# SmartSwitchController.net
KiCad netlist of a schematic drawn in EAGLE
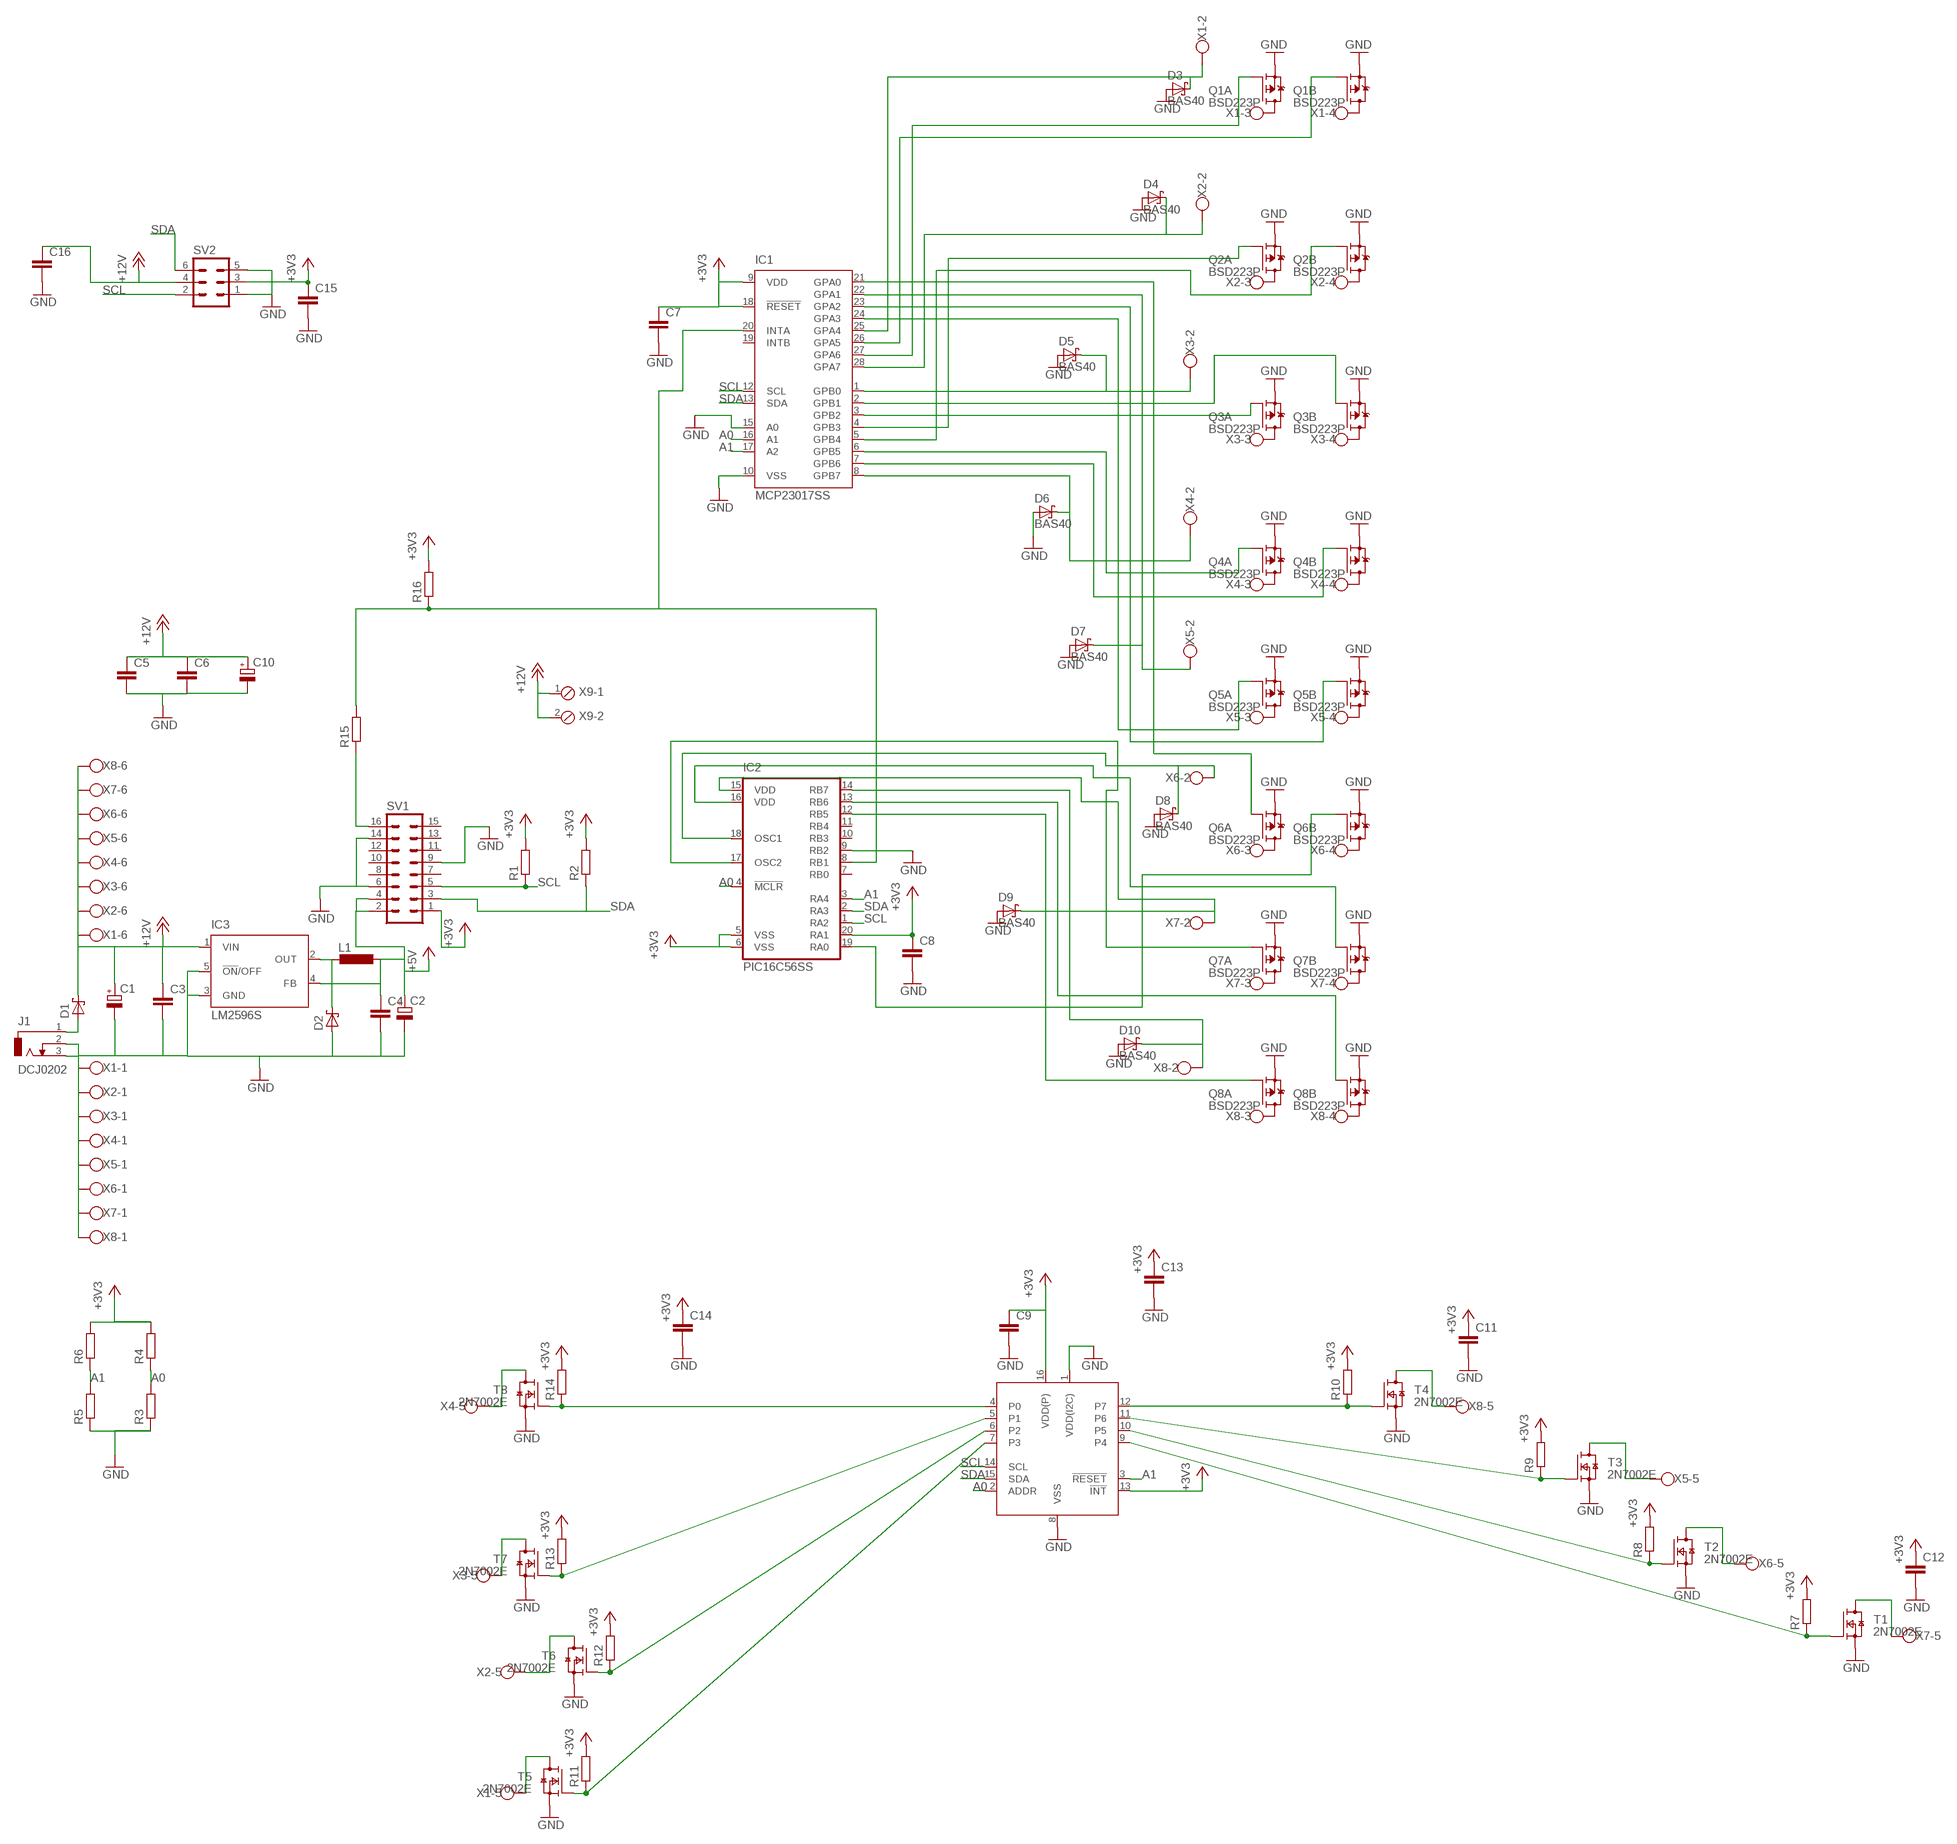
[diagram p0: schematic, sheet 1]

(export (version "E")
  (design (tool "Eeschema 10.0.6"))
  (components
    (comp (ref "C1")
      (value "CPOL-EUUD-6,3X7,7")
      (footprint "eagle-import:UD-6,3X7,7_NICHICON")
      (libsource (lib "eagle-import") (part "CPOL-EUUD-6,3X7,7"))
    )
    (comp (ref "C2")
      (value "CPOL-EUUD-10X10")
      (footprint "eagle-import:UD-10X10_NICHICON")
      (libsource (lib "eagle-import") (part "CPOL-EUUD-10X10"))
    )
    (comp (ref "C3")
      (value "C-EUC0603")
      (footprint "eagle-import:C0603")
      (libsource (lib "eagle-import") (part "C-EUC0603"))
    )
    (comp (ref "C4")
      (value "C-EUC0603")
      (footprint "eagle-import:C0603")
      (libsource (lib "eagle-import") (part "C-EUC0603"))
    )
    (comp (ref "C5")
      (value "C-EUC0603")
      (footprint "eagle-import:C0603")
      (libsource (lib "eagle-import") (part "C-EUC0603"))
    )
    (comp (ref "C6")
      (value "C-EUC0805")
      (footprint "eagle-import:C0805")
      (libsource (lib "eagle-import") (part "C-EUC0805"))
    )
    (comp (ref "C7")
      (value "C-EUC0603")
      (footprint "eagle-import:C0603")
      (libsource (lib "eagle-import") (part "C-EUC0603"))
    )
    (comp (ref "C8")
      (value "C-EUC0603")
      (footprint "eagle-import:C0603")
      (libsource (lib "eagle-import") (part "C-EUC0603"))
    )
    (comp (ref "C9")
      (value "C-EUC0603")
      (footprint "eagle-import:C0603")
      (libsource (lib "eagle-import") (part "C-EUC0603"))
    )
    (comp (ref "C10")
      (value "CPOL-EUUD-6,3X7,7")
      (footprint "eagle-import:UD-6,3X7,7_NICHICON")
      (libsource (lib "eagle-import") (part "CPOL-EUUD-6,3X7,7"))
    )
    (comp (ref "C11")
      (value "C-EUC0603")
      (footprint "eagle-import:C0603")
      (libsource (lib "eagle-import") (part "C-EUC0603"))
    )
    (comp (ref "C12")
      (value "C-EUC0603")
      (footprint "eagle-import:C0603")
      (libsource (lib "eagle-import") (part "C-EUC0603"))
    )
    (comp (ref "C13")
      (value "C-EUC0805")
      (footprint "eagle-import:C0805")
      (libsource (lib "eagle-import") (part "C-EUC0805"))
    )
    (comp (ref "C14")
      (value "C-EUC0805")
      (footprint "eagle-import:C0805")
      (libsource (lib "eagle-import") (part "C-EUC0805"))
    )
    (comp (ref "C15")
      (value "C-EUC0805")
      (footprint "eagle-import:C0805")
      (libsource (lib "eagle-import") (part "C-EUC0805"))
    )
    (comp (ref "C16")
      (value "C-EUC0805")
      (footprint "eagle-import:C0805")
      (libsource (lib "eagle-import") (part "C-EUC0805"))
    )
    (comp (ref "D1")
      (value "SCHOTTKY-DIODESMC")
      (footprint "eagle-import:SMC")
      (libsource (lib "eagle-import") (part "SCHOTTKY-DIODESMC"))
    )
    (comp (ref "D2")
      (value "SCHOTTKY-DIODESMC")
      (footprint "eagle-import:SMC")
      (libsource (lib "eagle-import") (part "SCHOTTKY-DIODESMC"))
    )
    (comp (ref "D3")
      (value "BAS40")
      (footprint "eagle-import:SOT23")
      (libsource (lib "eagle-import") (part "BAS40"))
    )
    (comp (ref "D4")
      (value "BAS40")
      (footprint "eagle-import:SOT23")
      (libsource (lib "eagle-import") (part "BAS40"))
    )
    (comp (ref "D5")
      (value "BAS40")
      (footprint "eagle-import:SOT23")
      (libsource (lib "eagle-import") (part "BAS40"))
    )
    (comp (ref "D6")
      (value "BAS40")
      (footprint "eagle-import:SOT23")
      (libsource (lib "eagle-import") (part "BAS40"))
    )
    (comp (ref "D7")
      (value "BAS40")
      (footprint "eagle-import:SOT23")
      (libsource (lib "eagle-import") (part "BAS40"))
    )
    (comp (ref "D8")
      (value "BAS40")
      (footprint "eagle-import:SOT23")
      (libsource (lib "eagle-import") (part "BAS40"))
    )
    (comp (ref "D9")
      (value "BAS40")
      (footprint "eagle-import:SOT23")
      (libsource (lib "eagle-import") (part "BAS40"))
    )
    (comp (ref "D10")
      (value "BAS40")
      (footprint "eagle-import:SOT23")
      (libsource (lib "eagle-import") (part "BAS40"))
    )
    (comp (ref "IC1")
      (value "MCP23017SS")
      (footprint "eagle-import:SSOP28")
      (fields (field (name "MF") "MICROCHIP") (field (name "MPN") "MCP23017-E/SS"))
      (libsource (lib "eagle-import") (part "MCP23017SS"))
    )
    (comp (ref "IC2")
      (value "PIC16C56SS")
      (footprint "eagle-import:SSOP20")
      (fields (field (name "MF") "MICROCHIP") (field (name "MPN") "PIC16C56A-04/SS"))
      (libsource (lib "eagle-import") (part "PIC16C56SS"))
    )
    (comp (ref "IC3")
      (value "LM2596S")
      (footprint "eagle-import:TO263-5")
      (fields (field (name "MF") "NATIONAL SEMICONDUCTOR") (field (name "MPN") "LM2596S-ADJ/NOPB"))
      (libsource (lib "eagle-import") (part "LM2596S"))
    )
    (comp (ref "J1")
      (value "DCJ0202")
      (footprint "eagle-import:DCJ0202")
      (libsource (lib "eagle-import") (part "DCJ0202"))
    )
    (comp (ref "L1")
      (value "L-EUL5650M")
      (footprint "eagle-import:L5650M")
      (libsource (lib "eagle-import") (part "L-EUL5650M"))
    )
    (comp (ref "Q1")
      (value "BSD223P")
      (footprint "eagle-import:SOT363_INFINEON")
      (libsource (lib "eagle-import") (part "BSD223P"))
    )
    (comp (ref "Q2")
      (value "BSD223P")
      (footprint "eagle-import:SOT363_INFINEON")
      (libsource (lib "eagle-import") (part "BSD223P"))
    )
    (comp (ref "Q3")
      (value "BSD223P")
      (footprint "eagle-import:SOT363_INFINEON")
      (libsource (lib "eagle-import") (part "BSD223P"))
    )
    (comp (ref "Q4")
      (value "BSD223P")
      (footprint "eagle-import:SOT363_INFINEON")
      (libsource (lib "eagle-import") (part "BSD223P"))
    )
    (comp (ref "Q5")
      (value "BSD223P")
      (footprint "eagle-import:SOT363_INFINEON")
      (libsource (lib "eagle-import") (part "BSD223P"))
    )
    (comp (ref "Q6")
      (value "BSD223P")
      (footprint "eagle-import:SOT363_INFINEON")
      (libsource (lib "eagle-import") (part "BSD223P"))
    )
    (comp (ref "Q7")
      (value "BSD223P")
      (footprint "eagle-import:SOT363_INFINEON")
      (libsource (lib "eagle-import") (part "BSD223P"))
    )
    (comp (ref "Q8")
      (value "BSD223P")
      (footprint "eagle-import:SOT363_INFINEON")
      (libsource (lib "eagle-import") (part "BSD223P"))
    )
    (comp (ref "R1")
      (value "R-EU_R0603")
      (footprint "eagle-import:R0603")
      (libsource (lib "eagle-import") (part "R-EU_R0603"))
    )
    (comp (ref "R2")
      (value "R-EU_R0603")
      (footprint "eagle-import:R0603")
      (libsource (lib "eagle-import") (part "R-EU_R0603"))
    )
    (comp (ref "R3")
      (value "R-EU_R0402")
      (footprint "eagle-import:R0402")
      (libsource (lib "eagle-import") (part "R-EU_R0402"))
    )
    (comp (ref "R4")
      (value "R-EU_R0402")
      (footprint "eagle-import:R0402")
      (libsource (lib "eagle-import") (part "R-EU_R0402"))
    )
    (comp (ref "R5")
      (value "R-EU_R0402")
      (footprint "eagle-import:R0402")
      (libsource (lib "eagle-import") (part "R-EU_R0402"))
    )
    (comp (ref "R6")
      (value "R-EU_R0402")
      (footprint "eagle-import:R0402")
      (libsource (lib "eagle-import") (part "R-EU_R0402"))
    )
    (comp (ref "R7")
      (value "R-EU_R0402")
      (footprint "eagle-import:R0402")
      (libsource (lib "eagle-import") (part "R-EU_R0402"))
    )
    (comp (ref "R8")
      (value "R-EU_R0402")
      (footprint "eagle-import:R0402")
      (libsource (lib "eagle-import") (part "R-EU_R0402"))
    )
    (comp (ref "R9")
      (value "R-EU_R0402")
      (footprint "eagle-import:R0402")
      (libsource (lib "eagle-import") (part "R-EU_R0402"))
    )
    (comp (ref "R10")
      (value "R-EU_R0402")
      (footprint "eagle-import:R0402")
      (libsource (lib "eagle-import") (part "R-EU_R0402"))
    )
    (comp (ref "R11")
      (value "R-EU_R0402")
      (footprint "eagle-import:R0402")
      (libsource (lib "eagle-import") (part "R-EU_R0402"))
    )
    (comp (ref "R12")
      (value "R-EU_R0402")
      (footprint "eagle-import:R0402")
      (libsource (lib "eagle-import") (part "R-EU_R0402"))
    )
    (comp (ref "R13")
      (value "R-EU_R0402")
      (footprint "eagle-import:R0402")
      (libsource (lib "eagle-import") (part "R-EU_R0402"))
    )
    (comp (ref "R14")
      (value "R-EU_R0402")
      (footprint "eagle-import:R0402")
      (libsource (lib "eagle-import") (part "R-EU_R0402"))
    )
    (comp (ref "R15")
      (value "R-EU_R0603")
      (footprint "eagle-import:R0603")
      (libsource (lib "eagle-import") (part "R-EU_R0603"))
    )
    (comp (ref "R16")
      (value "R-EU_R0603")
      (footprint "eagle-import:R0603")
      (libsource (lib "eagle-import") (part "R-EU_R0603"))
    )
    (comp (ref "SV1")
      (value "MA08-2")
      (footprint "eagle-import:MA08-2")
      (libsource (lib "eagle-import") (part "MA08-2"))
    )
    (comp (ref "SV2")
      (value "MA03-2")
      (footprint "eagle-import:MA03-2")
      (libsource (lib "eagle-import") (part "MA03-2"))
    )
    (comp (ref "T1")
      (value "2N7002E")
      (footprint "eagle-import:SOT23")
      (libsource (lib "eagle-import") (part "2N7002E"))
    )
    (comp (ref "T2")
      (value "2N7002E")
      (footprint "eagle-import:SOT23")
      (libsource (lib "eagle-import") (part "2N7002E"))
    )
    (comp (ref "T3")
      (value "2N7002E")
      (footprint "eagle-import:SOT23")
      (libsource (lib "eagle-import") (part "2N7002E"))
    )
    (comp (ref "T4")
      (value "2N7002E")
      (footprint "eagle-import:SOT23")
      (libsource (lib "eagle-import") (part "2N7002E"))
    )
    (comp (ref "T5")
      (value "2N7002E")
      (footprint "eagle-import:SOT23")
      (libsource (lib "eagle-import") (part "2N7002E"))
    )
    (comp (ref "T6")
      (value "2N7002E")
      (footprint "eagle-import:SOT23")
      (libsource (lib "eagle-import") (part "2N7002E"))
    )
    (comp (ref "T7")
      (value "2N7002E")
      (footprint "eagle-import:SOT23")
      (libsource (lib "eagle-import") (part "2N7002E"))
    )
    (comp (ref "T8")
      (value "2N7002E")
      (footprint "eagle-import:SOT23")
      (libsource (lib "eagle-import") (part "2N7002E"))
    )
    (comp (ref "U1")
      (value "PCAL6408APW")
      (footprint "eagle-import:SOT403-1")
      (libsource (lib "eagle-import") (part "PCAL6408APW"))
    )
    (comp (ref "X1")
      (value "W237-6")
      (footprint "eagle-import:W237-6")
      (libsource (lib "eagle-import") (part "W237-6"))
    )
    (comp (ref "X2")
      (value "W237-6")
      (footprint "eagle-import:W237-6")
      (libsource (lib "eagle-import") (part "W237-6"))
    )
    (comp (ref "X3")
      (value "W237-6")
      (footprint "eagle-import:W237-6")
      (libsource (lib "eagle-import") (part "W237-6"))
    )
    (comp (ref "X4")
      (value "W237-6")
      (footprint "eagle-import:W237-6")
      (libsource (lib "eagle-import") (part "W237-6"))
    )
    (comp (ref "X5")
      (value "W237-6")
      (footprint "eagle-import:W237-6")
      (libsource (lib "eagle-import") (part "W237-6"))
    )
    (comp (ref "X6")
      (value "W237-6")
      (footprint "eagle-import:W237-6")
      (libsource (lib "eagle-import") (part "W237-6"))
    )
    (comp (ref "X7")
      (value "W237-6")
      (footprint "eagle-import:W237-6")
      (libsource (lib "eagle-import") (part "W237-6"))
    )
    (comp (ref "X8")
      (value "W237-6")
      (footprint "eagle-import:W237-6")
      (libsource (lib "eagle-import") (part "W237-6"))
    )
    (comp (ref "X9")
      (value "MPT2")
      (footprint "eagle-import:2POL254")
      (libsource (lib "eagle-import") (part "MPT2"))
    )
  )
  (nets
    (net (code "1") (name "+3V3") (class "Default")
      (node (ref "C11") (pin "1") (pinfunction "1_1") (pintype "passive"))
      (node (ref "C12") (pin "1") (pinfunction "1_1") (pintype "passive"))
      (node (ref "C13") (pin "1") (pinfunction "1_1") (pintype "passive"))
      (node (ref "C14") (pin "1") (pinfunction "1_1") (pintype "passive"))
      (node (ref "C15") (pin "1") (pinfunction "1_1") (pintype "passive"))
      (node (ref "C7") (pin "1") (pinfunction "1_1") (pintype "passive"))
      (node (ref "C8") (pin "1") (pinfunction "1_1") (pintype "passive"))
      (node (ref "C9") (pin "1") (pinfunction "1_1") (pintype "passive"))
      (node (ref "IC1") (pin "18") (pinfunction "~{RESET}_18") (pintype "input"))
      (node (ref "IC1") (pin "9") (pinfunction "VDD_9") (pintype "power_in"))
      (node (ref "IC2") (pin "20") (pinfunction "RA1_20") (pintype "bidirectional"))
      (node (ref "IC2") (pin "5") (pinfunction "VSS_5") (pintype "power_in"))
      (node (ref "IC2") (pin "6") (pinfunction "VSS_6") (pintype "power_in"))
      (node (ref "R1") (pin "2") (pinfunction "2_2") (pintype "passive"))
      (node (ref "R10") (pin "2") (pinfunction "2_2") (pintype "passive"))
      (node (ref "R11") (pin "2") (pinfunction "2_2") (pintype "passive"))
      (node (ref "R12") (pin "2") (pinfunction "2_2") (pintype "passive"))
      (node (ref "R13") (pin "2") (pinfunction "2_2") (pintype "passive"))
      (node (ref "R14") (pin "2") (pinfunction "2_2") (pintype "passive"))
      (node (ref "R16") (pin "2") (pinfunction "2_2") (pintype "passive"))
      (node (ref "R2") (pin "2") (pinfunction "2_2") (pintype "passive"))
      (node (ref "R4") (pin "2") (pinfunction "2_2") (pintype "passive"))
      (node (ref "R6") (pin "2") (pinfunction "2_2") (pintype "passive"))
      (node (ref "R7") (pin "2") (pinfunction "2_2") (pintype "passive"))
      (node (ref "R8") (pin "2") (pinfunction "2_2") (pintype "passive"))
      (node (ref "R9") (pin "2") (pinfunction "2_2") (pintype "passive"))
      (node (ref "SV1") (pin "1") (pinfunction "1_1") (pintype "passive"))
      (node (ref "SV2") (pin "3") (pinfunction "3_3") (pintype "passive"))
      (node (ref "U1") (pin "13") (pinfunction "~{INT}_13") (pintype "output"))
      (node (ref "U1") (pin "16") (pinfunction "VDD(P)_16") (pintype "power_in"))
    )
    (net (code "2") (name "+5V") (class "Default")
      (node (ref "C2") (pin "+") (pinfunction "+_+") (pintype "passive"))
      (node (ref "C4") (pin "1") (pinfunction "1_1") (pintype "passive"))
      (node (ref "IC3") (pin "4") (pinfunction "FB_4") (pintype "input"))
      (node (ref "L1") (pin "1") (pinfunction "1_1") (pintype "passive"))
      (node (ref "SV1") (pin "2") (pinfunction "2_2") (pintype "passive"))
      (node (ref "SV1") (pin "4") (pinfunction "4_4") (pintype "passive"))
    )
    (net (code "3") (name "+12V") (class "Default")
      (node (ref "C1") (pin "+") (pinfunction "+_+") (pintype "passive"))
      (node (ref "C10") (pin "+") (pinfunction "+_+") (pintype "passive"))
      (node (ref "C16") (pin "1") (pinfunction "1_1") (pintype "passive"))
      (node (ref "C3") (pin "1") (pinfunction "1_1") (pintype "passive"))
      (node (ref "C5") (pin "1") (pinfunction "1_1") (pintype "passive"))
      (node (ref "C6") (pin "1") (pinfunction "1_1") (pintype "passive"))
      (node (ref "D1") (pin "C") (pinfunction "C_C") (pintype "passive"))
      (node (ref "IC3") (pin "1") (pinfunction "VIN_1") (pintype "input"))
      (node (ref "SV2") (pin "4") (pinfunction "4_4") (pintype "passive"))
      (node (ref "X1") (pin "6") (pinfunction "KL_6") (pintype "passive"))
      (node (ref "X2") (pin "6") (pinfunction "KL_6") (pintype "passive"))
      (node (ref "X3") (pin "6") (pinfunction "KL_6") (pintype "passive"))
      (node (ref "X4") (pin "6") (pinfunction "KL_6") (pintype "passive"))
      (node (ref "X5") (pin "6") (pinfunction "KL_6") (pintype "passive"))
      (node (ref "X6") (pin "6") (pinfunction "KL_6") (pintype "passive"))
      (node (ref "X7") (pin "6") (pinfunction "KL_6") (pintype "passive"))
      (node (ref "X8") (pin "6") (pinfunction "KL_6") (pintype "passive"))
      (node (ref "X9") (pin "1") (pinfunction "1_1") (pintype "passive"))
      (node (ref "X9") (pin "2") (pinfunction "1_2") (pintype "passive"))
    )
    (net (code "4") (name "/A0") (class "Default")
      (node (ref "IC1") (pin "16") (pinfunction "A1_16") (pintype "input"))
      (node (ref "IC2") (pin "4") (pinfunction "~{MCLR}_4") (pintype "input"))
      (node (ref "R3") (pin "2") (pinfunction "2_2") (pintype "passive"))
      (node (ref "R4") (pin "1") (pinfunction "1_1") (pintype "passive"))
      (node (ref "U1") (pin "2") (pinfunction "ADDR_2") (pintype "input"))
    )
    (net (code "5") (name "/A1") (class "Default")
      (node (ref "IC1") (pin "17") (pinfunction "A2_17") (pintype "input"))
      (node (ref "IC2") (pin "3") (pinfunction "RA4_3") (pintype "bidirectional"))
      (node (ref "R5") (pin "2") (pinfunction "2_2") (pintype "passive"))
      (node (ref "R6") (pin "1") (pinfunction "1_1") (pintype "passive"))
      (node (ref "U1") (pin "3") (pinfunction "~{RESET}_3") (pintype "input"))
    )
    (net (code "6") (name "/SCL") (class "Default")
      (node (ref "IC1") (pin "12") (pinfunction "SCL_12") (pintype "input"))
      (node (ref "IC2") (pin "1") (pinfunction "RA2_1") (pintype "bidirectional"))
      (node (ref "R1") (pin "1") (pinfunction "1_1") (pintype "passive"))
      (node (ref "SV1") (pin "5") (pinfunction "5_5") (pintype "passive"))
      (node (ref "SV2") (pin "2") (pinfunction "2_2") (pintype "passive"))
      (node (ref "U1") (pin "14") (pinfunction "SCL_14") (pintype "bidirectional"))
    )
    (net (code "7") (name "/SDA") (class "Default")
      (node (ref "IC1") (pin "13") (pinfunction "SDA_13") (pintype "bidirectional"))
      (node (ref "IC2") (pin "2") (pinfunction "RA3_2") (pintype "bidirectional"))
      (node (ref "R2") (pin "1") (pinfunction "1_1") (pintype "passive"))
      (node (ref "SV1") (pin "3") (pinfunction "3_3") (pintype "passive"))
      (node (ref "SV2") (pin "6") (pinfunction "6_6") (pintype "passive"))
      (node (ref "U1") (pin "15") (pinfunction "SDA_15") (pintype "bidirectional"))
    )
    (net (code "8") (name "GND") (class "Default")
      (node (ref "C1") (pin "-") (pinfunction "-_-") (pintype "passive"))
      (node (ref "C10") (pin "-") (pinfunction "-_-") (pintype "passive"))
      (node (ref "C11") (pin "2") (pinfunction "2_2") (pintype "passive"))
      (node (ref "C12") (pin "2") (pinfunction "2_2") (pintype "passive"))
      (node (ref "C13") (pin "2") (pinfunction "2_2") (pintype "passive"))
      (node (ref "C14") (pin "2") (pinfunction "2_2") (pintype "passive"))
      (node (ref "C15") (pin "2") (pinfunction "2_2") (pintype "passive"))
      (node (ref "C16") (pin "2") (pinfunction "2_2") (pintype "passive"))
      (node (ref "C2") (pin "-") (pinfunction "-_-") (pintype "passive"))
      (node (ref "C3") (pin "2") (pinfunction "2_2") (pintype "passive"))
      (node (ref "C4") (pin "2") (pinfunction "2_2") (pintype "passive"))
      (node (ref "C5") (pin "2") (pinfunction "2_2") (pintype "passive"))
      (node (ref "C6") (pin "2") (pinfunction "2_2") (pintype "passive"))
      (node (ref "C7") (pin "2") (pinfunction "2_2") (pintype "passive"))
      (node (ref "C8") (pin "2") (pinfunction "2_2") (pintype "passive"))
      (node (ref "C9") (pin "2") (pinfunction "2_2") (pintype "passive"))
      (node (ref "D10") (pin "1") (pinfunction "A_1") (pintype "passive"))
      (node (ref "D2") (pin "A") (pinfunction "A_A") (pintype "passive"))
      (node (ref "D3") (pin "1") (pinfunction "A_1") (pintype "passive"))
      (node (ref "D4") (pin "1") (pinfunction "A_1") (pintype "passive"))
      (node (ref "D5") (pin "1") (pinfunction "A_1") (pintype "passive"))
      (node (ref "D6") (pin "1") (pinfunction "A_1") (pintype "passive"))
      (node (ref "D7") (pin "1") (pinfunction "A_1") (pintype "passive"))
      (node (ref "D8") (pin "1") (pinfunction "A_1") (pintype "passive"))
      (node (ref "D9") (pin "1") (pinfunction "A_1") (pintype "passive"))
      (node (ref "IC1") (pin "10") (pinfunction "VSS_10") (pintype "power_in"))
      (node (ref "IC1") (pin "15") (pinfunction "A0_15") (pintype "input"))
      (node (ref "IC2") (pin "9") (pinfunction "RB2_9") (pintype "bidirectional"))
      (node (ref "IC3") (pin "3") (pinfunction "GND_3") (pintype "power_in"))
      (node (ref "IC3") (pin "5") (pinfunction "~{ON}/OFF_5") (pintype "input"))
      (node (ref "J1") (pin "2") (pinfunction "2_2") (pintype "passive"))
      (node (ref "J1") (pin "3") (pinfunction "3_3") (pintype "passive"))
      (node (ref "Q1") (pin "1") (pinfunction "S_1") (pintype "passive"))
      (node (ref "Q1") (pin "4") (pinfunction "S_4") (pintype "passive"))
      (node (ref "Q2") (pin "1") (pinfunction "S_1") (pintype "passive"))
      (node (ref "Q2") (pin "4") (pinfunction "S_4") (pintype "passive"))
      (node (ref "Q3") (pin "1") (pinfunction "S_1") (pintype "passive"))
      (node (ref "Q3") (pin "4") (pinfunction "S_4") (pintype "passive"))
      (node (ref "Q4") (pin "1") (pinfunction "S_1") (pintype "passive"))
      (node (ref "Q4") (pin "4") (pinfunction "S_4") (pintype "passive"))
      (node (ref "Q5") (pin "1") (pinfunction "S_1") (pintype "passive"))
      (node (ref "Q5") (pin "4") (pinfunction "S_4") (pintype "passive"))
      (node (ref "Q6") (pin "1") (pinfunction "S_1") (pintype "passive"))
      (node (ref "Q6") (pin "4") (pinfunction "S_4") (pintype "passive"))
      (node (ref "Q7") (pin "1") (pinfunction "S_1") (pintype "passive"))
      (node (ref "Q7") (pin "4") (pinfunction "S_4") (pintype "passive"))
      (node (ref "Q8") (pin "1") (pinfunction "S_1") (pintype "passive"))
      (node (ref "Q8") (pin "4") (pinfunction "S_4") (pintype "passive"))
      (node (ref "R3") (pin "1") (pinfunction "1_1") (pintype "passive"))
      (node (ref "R5") (pin "1") (pinfunction "1_1") (pintype "passive"))
      (node (ref "SV1") (pin "14") (pinfunction "14_14") (pintype "passive"))
      (node (ref "SV1") (pin "6") (pinfunction "6_6") (pintype "passive"))
      (node (ref "SV1") (pin "9") (pinfunction "9_9") (pintype "passive"))
      (node (ref "SV2") (pin "1") (pinfunction "1_1") (pintype "passive"))
      (node (ref "SV2") (pin "5") (pinfunction "5_5") (pintype "passive"))
      (node (ref "T1") (pin "2") (pinfunction "S_2") (pintype "passive"))
      (node (ref "T2") (pin "2") (pinfunction "S_2") (pintype "passive"))
      (node (ref "T3") (pin "2") (pinfunction "S_2") (pintype "passive"))
      (node (ref "T4") (pin "2") (pinfunction "S_2") (pintype "passive"))
      (node (ref "T5") (pin "2") (pinfunction "S_2") (pintype "passive"))
      (node (ref "T6") (pin "2") (pinfunction "S_2") (pintype "passive"))
      (node (ref "T7") (pin "2") (pinfunction "S_2") (pintype "passive"))
      (node (ref "T8") (pin "2") (pinfunction "S_2") (pintype "passive"))
      (node (ref "U1") (pin "1") (pinfunction "VDD(I2C)_1") (pintype "power_in"))
      (node (ref "U1") (pin "8") (pinfunction "VSS_8") (pintype "bidirectional"))
      (node (ref "X1") (pin "1") (pinfunction "KL_1") (pintype "passive"))
      (node (ref "X2") (pin "1") (pinfunction "KL_1") (pintype "passive"))
      (node (ref "X3") (pin "1") (pinfunction "KL_1") (pintype "passive"))
      (node (ref "X4") (pin "1") (pinfunction "KL_1") (pintype "passive"))
      (node (ref "X5") (pin "1") (pinfunction "KL_1") (pintype "passive"))
      (node (ref "X6") (pin "1") (pinfunction "KL_1") (pintype "passive"))
      (node (ref "X7") (pin "1") (pinfunction "KL_1") (pintype "passive"))
      (node (ref "X8") (pin "1") (pinfunction "KL_1") (pintype "passive"))
    )
    (net (code "9") (name "Net-(D1-PadA)") (class "Default")
      (node (ref "D1") (pin "A") (pinfunction "A_A") (pintype "passive"))
      (node (ref "J1") (pin "1") (pinfunction "1_1") (pintype "passive"))
    )
    (net (code "10") (name "Net-(D3-C)") (class "Default")
      (node (ref "D3") (pin "3") (pinfunction "C_3") (pintype "passive"))
      (node (ref "IC1") (pin "25") (pinfunction "GPA4_25") (pintype "bidirectional"))
      (node (ref "X1") (pin "2") (pinfunction "KL_2") (pintype "passive"))
    )
    (net (code "11") (name "Net-(D4-C)") (class "Default")
      (node (ref "D4") (pin "3") (pinfunction "C_3") (pintype "passive"))
      (node (ref "IC1") (pin "28") (pinfunction "GPA7_28") (pintype "bidirectional"))
      (node (ref "X2") (pin "2") (pinfunction "KL_2") (pintype "passive"))
    )
    (net (code "12") (name "Net-(D5-C)") (class "Default")
      (node (ref "D5") (pin "3") (pinfunction "C_3") (pintype "passive"))
      (node (ref "IC1") (pin "1") (pinfunction "GPB0_1") (pintype "bidirectional"))
      (node (ref "X3") (pin "2") (pinfunction "KL_2") (pintype "passive"))
    )
    (net (code "13") (name "Net-(D6-C)") (class "Default")
      (node (ref "D6") (pin "3") (pinfunction "C_3") (pintype "passive"))
      (node (ref "IC1") (pin "8") (pinfunction "GPB7_8") (pintype "bidirectional"))
      (node (ref "X4") (pin "2") (pinfunction "KL_2") (pintype "passive"))
    )
    (net (code "14") (name "Net-(D7-C)") (class "Default")
      (node (ref "D7") (pin "3") (pinfunction "C_3") (pintype "passive"))
      (node (ref "IC1") (pin "22") (pinfunction "GPA1_22") (pintype "bidirectional"))
      (node (ref "X5") (pin "2") (pinfunction "KL_2") (pintype "passive"))
    )
    (net (code "15") (name "Net-(D8-C)") (class "Default")
      (node (ref "D8") (pin "3") (pinfunction "C_3") (pintype "passive"))
      (node (ref "IC2") (pin "18") (pinfunction "OSC1_18") (pintype "input"))
      (node (ref "X6") (pin "2") (pinfunction "KL_2") (pintype "passive"))
    )
    (net (code "16") (name "Net-(D9-C)") (class "Default")
      (node (ref "D9") (pin "3") (pinfunction "C_3") (pintype "passive"))
      (node (ref "IC2") (pin "15") (pinfunction "VDD_15") (pintype "power_in"))
      (node (ref "X7") (pin "2") (pinfunction "KL_2") (pintype "passive"))
    )
    (net (code "17") (name "Net-(D10-C)") (class "Default")
      (node (ref "D10") (pin "3") (pinfunction "C_3") (pintype "passive"))
      (node (ref "IC2") (pin "14") (pinfunction "RB7_14") (pintype "bidirectional"))
      (node (ref "X8") (pin "2") (pinfunction "KL_2") (pintype "passive"))
    )
    (net (code "18") (name "Net-(IC1-GPA0)") (class "Default")
      (node (ref "IC1") (pin "21") (pinfunction "GPA0_21") (pintype "bidirectional"))
      (node (ref "Q6") (pin "2") (pinfunction "G_2") (pintype "passive"))
    )
    (net (code "19") (name "Net-(IC1-GPA2)") (class "Default")
      (node (ref "IC1") (pin "23") (pinfunction "GPA2_23") (pintype "bidirectional"))
      (node (ref "Q5") (pin "5") (pinfunction "G_5") (pintype "passive"))
    )
    (net (code "20") (name "Net-(IC1-GPA3)") (class "Default")
      (node (ref "IC1") (pin "24") (pinfunction "GPA3_24") (pintype "bidirectional"))
      (node (ref "Q5") (pin "2") (pinfunction "G_2") (pintype "passive"))
    )
    (net (code "21") (name "Net-(IC1-GPA5)") (class "Default")
      (node (ref "IC1") (pin "26") (pinfunction "GPA5_26") (pintype "bidirectional"))
      (node (ref "Q1") (pin "5") (pinfunction "G_5") (pintype "passive"))
    )
    (net (code "22") (name "Net-(IC1-GPA6)") (class "Default")
      (node (ref "IC1") (pin "27") (pinfunction "GPA6_27") (pintype "bidirectional"))
      (node (ref "Q1") (pin "2") (pinfunction "G_2") (pintype "passive"))
    )
    (net (code "23") (name "Net-(IC1-GPB1)") (class "Default")
      (node (ref "IC1") (pin "2") (pinfunction "GPB1_2") (pintype "bidirectional"))
      (node (ref "Q3") (pin "5") (pinfunction "G_5") (pintype "passive"))
    )
    (net (code "24") (name "Net-(IC1-GPB2)") (class "Default")
      (node (ref "IC1") (pin "3") (pinfunction "GPB2_3") (pintype "bidirectional"))
      (node (ref "Q3") (pin "2") (pinfunction "G_2") (pintype "passive"))
    )
    (net (code "25") (name "Net-(IC1-GPB3)") (class "Default")
      (node (ref "IC1") (pin "4") (pinfunction "GPB3_4") (pintype "bidirectional"))
      (node (ref "Q2") (pin "2") (pinfunction "G_2") (pintype "passive"))
    )
    (net (code "26") (name "Net-(IC1-GPB4)") (class "Default")
      (node (ref "IC1") (pin "5") (pinfunction "GPB4_5") (pintype "bidirectional"))
      (node (ref "Q2") (pin "5") (pinfunction "G_5") (pintype "passive"))
    )
    (net (code "27") (name "Net-(IC1-GPB5)") (class "Default")
      (node (ref "IC1") (pin "6") (pinfunction "GPB5_6") (pintype "bidirectional"))
      (node (ref "Q4") (pin "2") (pinfunction "G_2") (pintype "passive"))
    )
    (net (code "28") (name "Net-(IC1-GPB6)") (class "Default")
      (node (ref "IC1") (pin "7") (pinfunction "GPB6_7") (pintype "bidirectional"))
      (node (ref "Q4") (pin "5") (pinfunction "G_5") (pintype "passive"))
    )
    (net (code "29") (name "Net-(IC1-INTA)") (class "Default")
      (node (ref "IC1") (pin "20") (pinfunction "INTA_20") (pintype "output"))
      (node (ref "IC2") (pin "8") (pinfunction "RB1_8") (pintype "bidirectional"))
      (node (ref "R15") (pin "2") (pinfunction "2_2") (pintype "passive"))
      (node (ref "R16") (pin "1") (pinfunction "1_1") (pintype "passive"))
    )
    (net (code "30") (name "Net-(IC2-OSC2)") (class "Default")
      (node (ref "IC2") (pin "17") (pinfunction "OSC2_17") (pintype "output"))
      (node (ref "Q7") (pin "2") (pinfunction "G_2") (pintype "passive"))
    )
    (net (code "31") (name "Net-(IC2-RA0)") (class "Default")
      (node (ref "IC2") (pin "19") (pinfunction "RA0_19") (pintype "bidirectional"))
      (node (ref "Q6") (pin "5") (pinfunction "G_5") (pintype "passive"))
    )
    (net (code "32") (name "Net-(IC2-RB5)") (class "Default")
      (node (ref "IC2") (pin "12") (pinfunction "RB5_12") (pintype "bidirectional"))
      (node (ref "Q8") (pin "2") (pinfunction "G_2") (pintype "passive"))
    )
    (net (code "33") (name "Net-(IC2-RB6)") (class "Default")
      (node (ref "IC2") (pin "13") (pinfunction "RB6_13") (pintype "bidirectional"))
      (node (ref "Q8") (pin "5") (pinfunction "G_5") (pintype "passive"))
    )
    (net (code "34") (name "Net-(IC3-OUT)") (class "Default")
      (node (ref "D2") (pin "C") (pinfunction "C_C") (pintype "passive"))
      (node (ref "IC3") (pin "2") (pinfunction "OUT_2") (pintype "output"))
      (node (ref "L1") (pin "2") (pinfunction "2_2") (pintype "passive"))
    )
    (net (code "35") (name "Net-(Q1A-D)") (class "Default")
      (node (ref "Q1") (pin "6") (pinfunction "D_6") (pintype "passive"))
      (node (ref "X1") (pin "3") (pinfunction "KL_3") (pintype "passive"))
    )
    (net (code "36") (name "Net-(Q1B-D)") (class "Default")
      (node (ref "Q1") (pin "3") (pinfunction "D_3") (pintype "passive"))
      (node (ref "X1") (pin "4") (pinfunction "KL_4") (pintype "passive"))
    )
    (net (code "37") (name "Net-(Q2A-D)") (class "Default")
      (node (ref "Q2") (pin "6") (pinfunction "D_6") (pintype "passive"))
      (node (ref "X2") (pin "3") (pinfunction "KL_3") (pintype "passive"))
    )
    (net (code "38") (name "Net-(Q2B-D)") (class "Default")
      (node (ref "Q2") (pin "3") (pinfunction "D_3") (pintype "passive"))
      (node (ref "X2") (pin "4") (pinfunction "KL_4") (pintype "passive"))
    )
    (net (code "39") (name "Net-(Q3A-D)") (class "Default")
      (node (ref "Q3") (pin "6") (pinfunction "D_6") (pintype "passive"))
      (node (ref "X3") (pin "3") (pinfunction "KL_3") (pintype "passive"))
    )
    (net (code "40") (name "Net-(Q3B-D)") (class "Default")
      (node (ref "Q3") (pin "3") (pinfunction "D_3") (pintype "passive"))
      (node (ref "X3") (pin "4") (pinfunction "KL_4") (pintype "passive"))
    )
    (net (code "41") (name "Net-(Q4A-D)") (class "Default")
      (node (ref "Q4") (pin "6") (pinfunction "D_6") (pintype "passive"))
      (node (ref "X4") (pin "3") (pinfunction "KL_3") (pintype "passive"))
    )
    (net (code "42") (name "Net-(Q4B-D)") (class "Default")
      (node (ref "Q4") (pin "3") (pinfunction "D_3") (pintype "passive"))
      (node (ref "X4") (pin "4") (pinfunction "KL_4") (pintype "passive"))
    )
    (net (code "43") (name "Net-(Q5A-D)") (class "Default")
      (node (ref "Q5") (pin "6") (pinfunction "D_6") (pintype "passive"))
      (node (ref "X5") (pin "3") (pinfunction "KL_3") (pintype "passive"))
    )
    (net (code "44") (name "Net-(Q5B-D)") (class "Default")
      (node (ref "Q5") (pin "3") (pinfunction "D_3") (pintype "passive"))
      (node (ref "X5") (pin "4") (pinfunction "KL_4") (pintype "passive"))
    )
    (net (code "45") (name "Net-(Q6A-D)") (class "Default")
      (node (ref "Q6") (pin "6") (pinfunction "D_6") (pintype "passive"))
      (node (ref "X6") (pin "3") (pinfunction "KL_3") (pintype "passive"))
    )
    (net (code "46") (name "Net-(Q6B-D)") (class "Default")
      (node (ref "Q6") (pin "3") (pinfunction "D_3") (pintype "passive"))
      (node (ref "X6") (pin "4") (pinfunction "KL_4") (pintype "passive"))
    )
    (net (code "47") (name "Net-(Q7A-D)") (class "Default")
      (node (ref "Q7") (pin "6") (pinfunction "D_6") (pintype "passive"))
      (node (ref "X7") (pin "3") (pinfunction "KL_3") (pintype "passive"))
    )
    (net (code "48") (name "Net-(Q7B-D)") (class "Default")
      (node (ref "Q7") (pin "3") (pinfunction "D_3") (pintype "passive"))
      (node (ref "X7") (pin "4") (pinfunction "KL_4") (pintype "passive"))
    )
    (net (code "49") (name "Net-(Q7B-G)") (class "Default")
      (node (ref "IC2") (pin "16") (pinfunction "VDD_16") (pintype "power_in"))
      (node (ref "Q7") (pin "5") (pinfunction "G_5") (pintype "passive"))
    )
    (net (code "50") (name "Net-(Q8A-D)") (class "Default")
      (node (ref "Q8") (pin "6") (pinfunction "D_6") (pintype "passive"))
      (node (ref "X8") (pin "3") (pinfunction "KL_3") (pintype "passive"))
    )
    (net (code "51") (name "Net-(Q8B-D)") (class "Default")
      (node (ref "Q8") (pin "3") (pinfunction "D_3") (pintype "passive"))
      (node (ref "X8") (pin "4") (pinfunction "KL_4") (pintype "passive"))
    )
    (net (code "52") (name "Net-(R15-Pad1)") (class "Default")
      (node (ref "R15") (pin "1") (pinfunction "1_1") (pintype "passive"))
      (node (ref "SV1") (pin "16") (pinfunction "16_16") (pintype "passive"))
    )
    (net (code "53") (name "Net-(T1-D)") (class "Default")
      (node (ref "T1") (pin "3") (pinfunction "D_3") (pintype "passive"))
      (node (ref "X7") (pin "5") (pinfunction "KL_5") (pintype "passive"))
    )
    (net (code "54") (name "Net-(T1-G)") (class "Default")
      (node (ref "R7") (pin "1") (pinfunction "1_1") (pintype "passive"))
      (node (ref "T1") (pin "1") (pinfunction "G_1") (pintype "passive"))
      (node (ref "U1") (pin "9") (pinfunction "P4_9") (pintype "bidirectional"))
    )
    (net (code "55") (name "Net-(T2-D)") (class "Default")
      (node (ref "T2") (pin "3") (pinfunction "D_3") (pintype "passive"))
      (node (ref "X6") (pin "5") (pinfunction "KL_5") (pintype "passive"))
    )
    (net (code "56") (name "Net-(T2-G)") (class "Default")
      (node (ref "R8") (pin "1") (pinfunction "1_1") (pintype "passive"))
      (node (ref "T2") (pin "1") (pinfunction "G_1") (pintype "passive"))
      (node (ref "U1") (pin "10") (pinfunction "P5_10") (pintype "bidirectional"))
    )
    (net (code "57") (name "Net-(T3-D)") (class "Default")
      (node (ref "T3") (pin "3") (pinfunction "D_3") (pintype "passive"))
      (node (ref "X5") (pin "5") (pinfunction "KL_5") (pintype "passive"))
    )
    (net (code "58") (name "Net-(T3-G)") (class "Default")
      (node (ref "R9") (pin "1") (pinfunction "1_1") (pintype "passive"))
      (node (ref "T3") (pin "1") (pinfunction "G_1") (pintype "passive"))
      (node (ref "U1") (pin "11") (pinfunction "P6_11") (pintype "bidirectional"))
    )
    (net (code "59") (name "Net-(T4-D)") (class "Default")
      (node (ref "T4") (pin "3") (pinfunction "D_3") (pintype "passive"))
      (node (ref "X8") (pin "5") (pinfunction "KL_5") (pintype "passive"))
    )
    (net (code "60") (name "Net-(T4-G)") (class "Default")
      (node (ref "R10") (pin "1") (pinfunction "1_1") (pintype "passive"))
      (node (ref "T4") (pin "1") (pinfunction "G_1") (pintype "passive"))
      (node (ref "U1") (pin "12") (pinfunction "P7_12") (pintype "bidirectional"))
    )
    (net (code "61") (name "Net-(T5-D)") (class "Default")
      (node (ref "T5") (pin "3") (pinfunction "D_3") (pintype "passive"))
      (node (ref "X1") (pin "5") (pinfunction "KL_5") (pintype "passive"))
    )
    (net (code "62") (name "Net-(T5-G)") (class "Default")
      (node (ref "R11") (pin "1") (pinfunction "1_1") (pintype "passive"))
      (node (ref "T5") (pin "1") (pinfunction "G_1") (pintype "passive"))
      (node (ref "U1") (pin "7") (pinfunction "P3_7") (pintype "bidirectional"))
    )
    (net (code "63") (name "Net-(T6-D)") (class "Default")
      (node (ref "T6") (pin "3") (pinfunction "D_3") (pintype "passive"))
      (node (ref "X2") (pin "5") (pinfunction "KL_5") (pintype "passive"))
    )
    (net (code "64") (name "Net-(T6-G)") (class "Default")
      (node (ref "R12") (pin "1") (pinfunction "1_1") (pintype "passive"))
      (node (ref "T6") (pin "1") (pinfunction "G_1") (pintype "passive"))
      (node (ref "U1") (pin "6") (pinfunction "P2_6") (pintype "bidirectional"))
    )
    (net (code "65") (name "Net-(T7-D)") (class "Default")
      (node (ref "T7") (pin "3") (pinfunction "D_3") (pintype "passive"))
      (node (ref "X3") (pin "5") (pinfunction "KL_5") (pintype "passive"))
    )
    (net (code "66") (name "Net-(T7-G)") (class "Default")
      (node (ref "R13") (pin "1") (pinfunction "1_1") (pintype "passive"))
      (node (ref "T7") (pin "1") (pinfunction "G_1") (pintype "passive"))
      (node (ref "U1") (pin "5") (pinfunction "P1_5") (pintype "bidirectional"))
    )
    (net (code "67") (name "Net-(T8-D)") (class "Default")
      (node (ref "T8") (pin "3") (pinfunction "D_3") (pintype "passive"))
      (node (ref "X4") (pin "5") (pinfunction "KL_5") (pintype "passive"))
    )
    (net (code "68") (name "Net-(T8-G)") (class "Default")
      (node (ref "R14") (pin "1") (pinfunction "1_1") (pintype "passive"))
      (node (ref "T8") (pin "1") (pinfunction "G_1") (pintype "passive"))
      (node (ref "U1") (pin "4") (pinfunction "P0_4") (pintype "bidirectional"))
    )
    (net (code "69") (name "unconnected-(IC1-INTB-Pad19)") (class "Default")
      (node (ref "IC1") (pin "19") (pinfunction "INTB_19") (pintype "output"))
    )
    (net (code "70") (name "unconnected-(IC2-RB0-Pad7)") (class "Default")
      (node (ref "IC2") (pin "7") (pinfunction "RB0_7") (pintype "bidirectional"))
    )
    (net (code "71") (name "unconnected-(IC2-RB3-Pad10)") (class "Default")
      (node (ref "IC2") (pin "10") (pinfunction "RB3_10") (pintype "bidirectional"))
    )
    (net (code "72") (name "unconnected-(IC2-RB4-Pad11)") (class "Default")
      (node (ref "IC2") (pin "11") (pinfunction "RB4_11") (pintype "bidirectional"))
    )
    (net (code "73") (name "unconnected-(SV1-Pad7)") (class "Default")
      (node (ref "SV1") (pin "7") (pinfunction "7_7") (pintype "passive"))
    )
    (net (code "74") (name "unconnected-(SV1-Pad8)") (class "Default")
      (node (ref "SV1") (pin "8") (pinfunction "8_8") (pintype "passive"))
    )
    (net (code "75") (name "unconnected-(SV1-Pad10)") (class "Default")
      (node (ref "SV1") (pin "10") (pinfunction "10_10") (pintype "passive"))
    )
    (net (code "76") (name "unconnected-(SV1-Pad11)") (class "Default")
      (node (ref "SV1") (pin "11") (pinfunction "11_11") (pintype "passive"))
    )
    (net (code "77") (name "unconnected-(SV1-Pad12)") (class "Default")
      (node (ref "SV1") (pin "12") (pinfunction "12_12") (pintype "passive"))
    )
    (net (code "78") (name "unconnected-(SV1-Pad13)") (class "Default")
      (node (ref "SV1") (pin "13") (pinfunction "13_13") (pintype "passive"))
    )
    (net (code "79") (name "unconnected-(SV1-Pad15)") (class "Default")
      (node (ref "SV1") (pin "15") (pinfunction "15_15") (pintype "passive"))
    )
  )
)
